# ETH_Design_ESP32.net
KiCad netlist of a schematic drawn in EAGLE
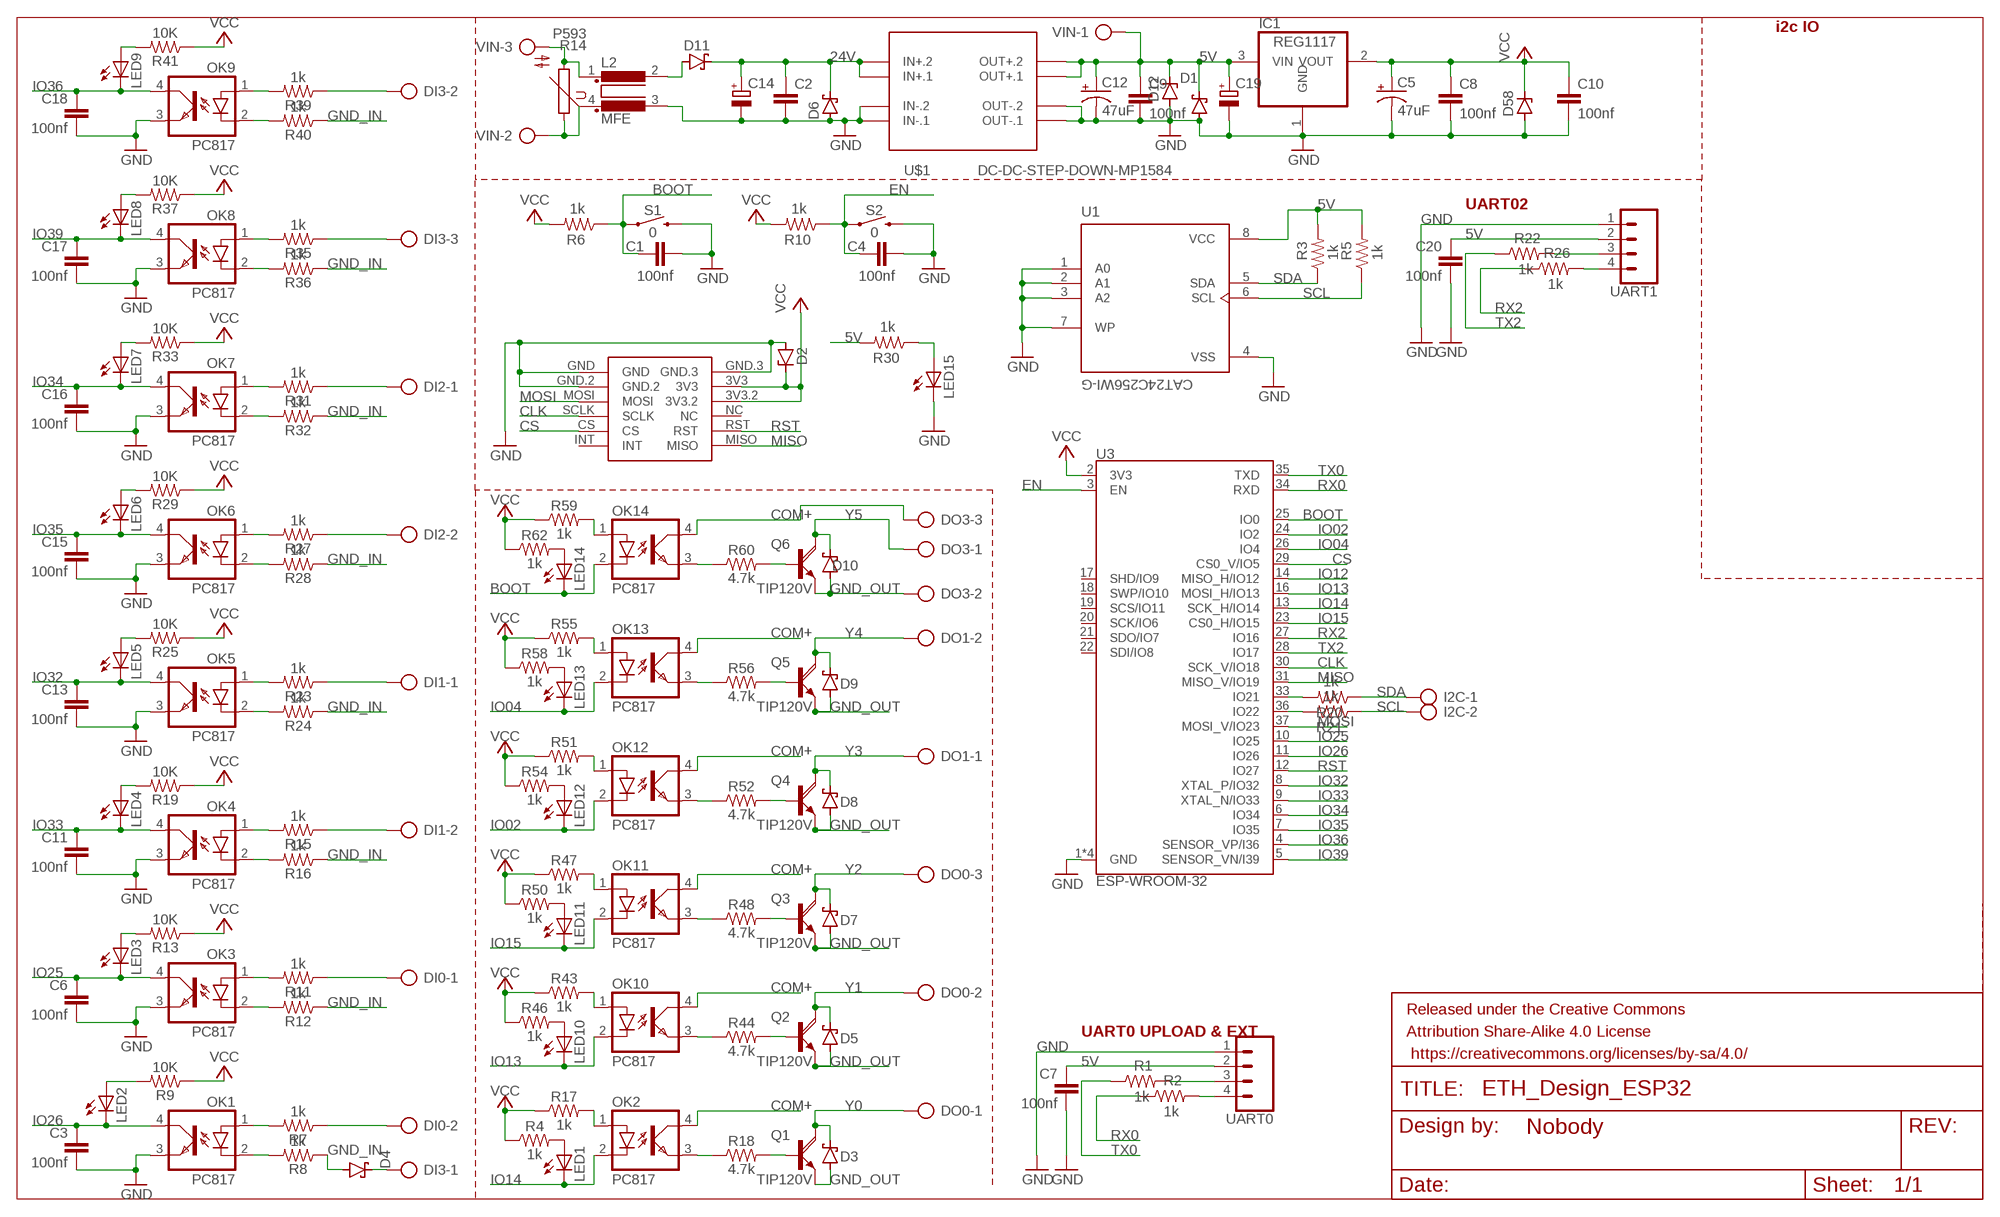
[diagram p0: schematic, sheet 1]

(export (version "E")
  (design (tool "Eeschema 10.0.6"))
  (components
    (comp (ref "C1")
      (value "100nf")
      (footprint "eagle-import:0805")
      (libsource (lib "eagle-import") (part "39NF-0805-50V-10%"))
    )
    (comp (ref "C2")
      (value "C-EUC1206K")
      (footprint "eagle-import:C1206K")
      (libsource (lib "eagle-import") (part "C-EUC1206K"))
    )
    (comp (ref "C3")
      (value "100nf")
      (footprint "eagle-import:0805")
      (libsource (lib "eagle-import") (part "39NF-0805-50V-10%"))
    )
    (comp (ref "C4")
      (value "100nf")
      (footprint "eagle-import:0805")
      (libsource (lib "eagle-import") (part "39NF-0805-50V-10%"))
    )
    (comp (ref "C5")
      (value "47uF")
      (footprint "eagle-import:EIA3528")
      (libsource (lib "eagle-import") (part "47UF-POLAR-EIA3528-10V-10%"))
    )
    (comp (ref "C6")
      (value "100nf")
      (footprint "eagle-import:0805")
      (libsource (lib "eagle-import") (part "39NF-0805-50V-10%"))
    )
    (comp (ref "C7")
      (value "100nf")
      (footprint "eagle-import:0805")
      (libsource (lib "eagle-import") (part "39NF-0805-50V-10%"))
    )
    (comp (ref "C8")
      (value "100nf")
      (footprint "eagle-import:0805")
      (libsource (lib "eagle-import") (part "39NF-0805-50V-10%"))
    )
    (comp (ref "C9")
      (value "100nf")
      (footprint "eagle-import:0805")
      (libsource (lib "eagle-import") (part "39NF-0805-50V-10%"))
    )
    (comp (ref "C10")
      (value "100nf")
      (footprint "eagle-import:0805")
      (libsource (lib "eagle-import") (part "39NF-0805-50V-10%"))
    )
    (comp (ref "C11")
      (value "100nf")
      (footprint "eagle-import:0805")
      (libsource (lib "eagle-import") (part "39NF-0805-50V-10%"))
    )
    (comp (ref "C12")
      (value "47uF")
      (footprint "eagle-import:EIA3528")
      (libsource (lib "eagle-import") (part "47UF-POLAR-EIA3528-10V-10%"))
    )
    (comp (ref "C13")
      (value "100nf")
      (footprint "eagle-import:0805")
      (libsource (lib "eagle-import") (part "39NF-0805-50V-10%"))
    )
    (comp (ref "C14")
      (value "CPOL-EUE2.5-7")
      (footprint "eagle-import:E2,5-7")
      (libsource (lib "eagle-import") (part "CPOL-EUE2.5-7"))
    )
    (comp (ref "C15")
      (value "100nf")
      (footprint "eagle-import:0805")
      (libsource (lib "eagle-import") (part "39NF-0805-50V-10%"))
    )
    (comp (ref "C16")
      (value "100nf")
      (footprint "eagle-import:0805")
      (libsource (lib "eagle-import") (part "39NF-0805-50V-10%"))
    )
    (comp (ref "C17")
      (value "100nf")
      (footprint "eagle-import:0805")
      (libsource (lib "eagle-import") (part "39NF-0805-50V-10%"))
    )
    (comp (ref "C18")
      (value "100nf")
      (footprint "eagle-import:0805")
      (libsource (lib "eagle-import") (part "39NF-0805-50V-10%"))
    )
    (comp (ref "C19")
      (value "CPOL-EUE2.5-7")
      (footprint "eagle-import:E2,5-7")
      (libsource (lib "eagle-import") (part "CPOL-EUE2.5-7"))
    )
    (comp (ref "C20")
      (value "100nf")
      (footprint "eagle-import:0805")
      (libsource (lib "eagle-import") (part "39NF-0805-50V-10%"))
    )
    (comp (ref "D1")
      (value "SCHOTTKY-DIODESMD")
      (footprint "eagle-import:SMB")
      (libsource (lib "eagle-import") (part "SCHOTTKY-DIODESMD"))
    )
    (comp (ref "D2")
      (value "ZENER-DIODESOD80C")
      (footprint "eagle-import:SOD80C")
      (libsource (lib "eagle-import") (part "ZENER-DIODESOD80C"))
    )
    (comp (ref "D3")
      (value "SCHOTTKY-DIODESMD")
      (footprint "eagle-import:SMB")
      (libsource (lib "eagle-import") (part "SCHOTTKY-DIODESMD"))
    )
    (comp (ref "D4")
      (value "SCHOTTKY-DIODESMD")
      (footprint "eagle-import:SMB")
      (libsource (lib "eagle-import") (part "SCHOTTKY-DIODESMD"))
    )
    (comp (ref "D5")
      (value "SCHOTTKY-DIODESMD")
      (footprint "eagle-import:SMB")
      (libsource (lib "eagle-import") (part "SCHOTTKY-DIODESMD"))
    )
    (comp (ref "D6")
      (value "SCHOTTKY-DIODESMD")
      (footprint "eagle-import:SMB")
      (libsource (lib "eagle-import") (part "SCHOTTKY-DIODESMD"))
    )
    (comp (ref "D7")
      (value "SCHOTTKY-DIODESMD")
      (footprint "eagle-import:SMB")
      (libsource (lib "eagle-import") (part "SCHOTTKY-DIODESMD"))
    )
    (comp (ref "D8")
      (value "SCHOTTKY-DIODESMD")
      (footprint "eagle-import:SMB")
      (libsource (lib "eagle-import") (part "SCHOTTKY-DIODESMD"))
    )
    (comp (ref "D9")
      (value "SCHOTTKY-DIODESMD")
      (footprint "eagle-import:SMB")
      (libsource (lib "eagle-import") (part "SCHOTTKY-DIODESMD"))
    )
    (comp (ref "D10")
      (value "SCHOTTKY-DIODESMD")
      (footprint "eagle-import:SMB")
      (libsource (lib "eagle-import") (part "SCHOTTKY-DIODESMD"))
    )
    (comp (ref "D11")
      (value "SCHOTTKY-DIODESMD")
      (footprint "eagle-import:SMB")
      (libsource (lib "eagle-import") (part "SCHOTTKY-DIODESMD"))
    )
    (comp (ref "D12")
      (value "ZENER-DIODESOD80C")
      (footprint "eagle-import:SOD80C")
      (libsource (lib "eagle-import") (part "ZENER-DIODESOD80C"))
    )
    (comp (ref "D58")
      (value "ZENER-DIODESOD80C")
      (footprint "eagle-import:SOD80C")
      (libsource (lib "eagle-import") (part "ZENER-DIODESOD80C"))
    )
    (comp (ref "DI0")
      (value "AK500/2")
      (footprint "eagle-import:AK500_2")
      (libsource (lib "eagle-import") (part "AK500/2"))
    )
    (comp (ref "DI1")
      (value "AK500/2")
      (footprint "eagle-import:AK500_2")
      (libsource (lib "eagle-import") (part "AK500/2"))
    )
    (comp (ref "DI2")
      (value "AK500/2")
      (footprint "eagle-import:AK500_2")
      (libsource (lib "eagle-import") (part "AK500/2"))
    )
    (comp (ref "DI3")
      (value "AK500/3")
      (footprint "eagle-import:AK500_3")
      (libsource (lib "eagle-import") (part "AK500/3"))
    )
    (comp (ref "DO0")
      (value "AK500/3")
      (footprint "eagle-import:AK500_3")
      (libsource (lib "eagle-import") (part "AK500/3"))
    )
    (comp (ref "DO1")
      (value "AK500/2")
      (footprint "eagle-import:AK500_2")
      (libsource (lib "eagle-import") (part "AK500/2"))
    )
    (comp (ref "DO3")
      (value "AK500/3")
      (footprint "eagle-import:AK500_3")
      (libsource (lib "eagle-import") (part "AK500/3"))
    )
    (comp (ref "FRAME1")
      (value "FRAME-LETTERNO_PACKAGE")
      (footprint "eagle-import:DUMMY")
      (fields (field (name "DESIGNER") "Nobody"))
      (libsource (lib "eagle-import") (part "FRAME-LETTERNO_PACKAGE"))
    )
    (comp (ref "I2C")
      (value "AK500/2")
      (footprint "eagle-import:AK500_2")
      (libsource (lib "eagle-import") (part "AK500/2"))
    )
    (comp (ref "IC1")
      (value "REG1117")
      (footprint "eagle-import:SOT223")
      (libsource (lib "eagle-import") (part "REG1117"))
    )
    (comp (ref "L2")
      (value "MFE")
      (footprint "eagle-import:MFE")
      (libsource (lib "eagle-import") (part "MFE"))
    )
    (comp (ref "LED1")
      (value "LEDCHIPLED_0805")
      (footprint "eagle-import:CHIPLED_0805")
      (libsource (lib "eagle-import") (part "LEDCHIPLED_0805"))
    )
    (comp (ref "LED2")
      (value "LEDCHIPLED_0805")
      (footprint "eagle-import:CHIPLED_0805")
      (libsource (lib "eagle-import") (part "LEDCHIPLED_0805"))
    )
    (comp (ref "LED3")
      (value "LEDCHIPLED_0805")
      (footprint "eagle-import:CHIPLED_0805")
      (libsource (lib "eagle-import") (part "LEDCHIPLED_0805"))
    )
    (comp (ref "LED4")
      (value "LEDCHIPLED_0805")
      (footprint "eagle-import:CHIPLED_0805")
      (libsource (lib "eagle-import") (part "LEDCHIPLED_0805"))
    )
    (comp (ref "LED5")
      (value "LEDCHIPLED_0805")
      (footprint "eagle-import:CHIPLED_0805")
      (libsource (lib "eagle-import") (part "LEDCHIPLED_0805"))
    )
    (comp (ref "LED6")
      (value "LEDCHIPLED_0805")
      (footprint "eagle-import:CHIPLED_0805")
      (libsource (lib "eagle-import") (part "LEDCHIPLED_0805"))
    )
    (comp (ref "LED7")
      (value "LEDCHIPLED_0805")
      (footprint "eagle-import:CHIPLED_0805")
      (libsource (lib "eagle-import") (part "LEDCHIPLED_0805"))
    )
    (comp (ref "LED8")
      (value "LEDCHIPLED_0805")
      (footprint "eagle-import:CHIPLED_0805")
      (libsource (lib "eagle-import") (part "LEDCHIPLED_0805"))
    )
    (comp (ref "LED9")
      (value "LEDCHIPLED_0805")
      (footprint "eagle-import:CHIPLED_0805")
      (libsource (lib "eagle-import") (part "LEDCHIPLED_0805"))
    )
    (comp (ref "LED10")
      (value "LEDCHIPLED_0805")
      (footprint "eagle-import:CHIPLED_0805")
      (libsource (lib "eagle-import") (part "LEDCHIPLED_0805"))
    )
    (comp (ref "LED11")
      (value "LEDCHIPLED_0805")
      (footprint "eagle-import:CHIPLED_0805")
      (libsource (lib "eagle-import") (part "LEDCHIPLED_0805"))
    )
    (comp (ref "LED12")
      (value "LEDCHIPLED_0805")
      (footprint "eagle-import:CHIPLED_0805")
      (libsource (lib "eagle-import") (part "LEDCHIPLED_0805"))
    )
    (comp (ref "LED13")
      (value "LEDCHIPLED_0805")
      (footprint "eagle-import:CHIPLED_0805")
      (libsource (lib "eagle-import") (part "LEDCHIPLED_0805"))
    )
    (comp (ref "LED14")
      (value "LEDCHIPLED_0805")
      (footprint "eagle-import:CHIPLED_0805")
      (libsource (lib "eagle-import") (part "LEDCHIPLED_0805"))
    )
    (comp (ref "LED15")
      (value "LEDCHIPLED_0805")
      (footprint "eagle-import:CHIPLED_0805")
      (libsource (lib "eagle-import") (part "LEDCHIPLED_0805"))
    )
    (comp (ref "OK1")
      (value "PC817")
      (footprint "eagle-import:DIL04")
      (fields (field (name "MPN") "PC817X4J000F"))
      (libsource (lib "eagle-import") (part "PC817"))
    )
    (comp (ref "OK2")
      (value "PC817")
      (footprint "eagle-import:DIL04")
      (fields (field (name "MPN") "PC817X4J000F"))
      (libsource (lib "eagle-import") (part "PC817"))
    )
    (comp (ref "OK3")
      (value "PC817")
      (footprint "eagle-import:DIL04")
      (fields (field (name "MPN") "PC817X4J000F"))
      (libsource (lib "eagle-import") (part "PC817"))
    )
    (comp (ref "OK4")
      (value "PC817")
      (footprint "eagle-import:DIL04")
      (fields (field (name "MPN") "PC817X4J000F"))
      (libsource (lib "eagle-import") (part "PC817"))
    )
    (comp (ref "OK5")
      (value "PC817")
      (footprint "eagle-import:DIL04")
      (fields (field (name "MPN") "PC817X4J000F"))
      (libsource (lib "eagle-import") (part "PC817"))
    )
    (comp (ref "OK6")
      (value "PC817")
      (footprint "eagle-import:DIL04")
      (fields (field (name "MPN") "PC817X4J000F"))
      (libsource (lib "eagle-import") (part "PC817"))
    )
    (comp (ref "OK7")
      (value "PC817")
      (footprint "eagle-import:DIL04")
      (fields (field (name "MPN") "PC817X4J000F"))
      (libsource (lib "eagle-import") (part "PC817"))
    )
    (comp (ref "OK8")
      (value "PC817")
      (footprint "eagle-import:DIL04")
      (fields (field (name "MPN") "PC817X4J000F"))
      (libsource (lib "eagle-import") (part "PC817"))
    )
    (comp (ref "OK9")
      (value "PC817")
      (footprint "eagle-import:DIL04")
      (fields (field (name "MPN") "PC817X4J000F"))
      (libsource (lib "eagle-import") (part "PC817"))
    )
    (comp (ref "OK10")
      (value "PC817")
      (footprint "eagle-import:DIL04")
      (fields (field (name "MPN") "PC817X4J000F"))
      (libsource (lib "eagle-import") (part "PC817"))
    )
    (comp (ref "OK11")
      (value "PC817")
      (footprint "eagle-import:DIL04")
      (fields (field (name "MPN") "PC817X4J000F"))
      (libsource (lib "eagle-import") (part "PC817"))
    )
    (comp (ref "OK12")
      (value "PC817")
      (footprint "eagle-import:DIL04")
      (fields (field (name "MPN") "PC817X4J000F"))
      (libsource (lib "eagle-import") (part "PC817"))
    )
    (comp (ref "OK13")
      (value "PC817")
      (footprint "eagle-import:DIL04")
      (fields (field (name "MPN") "PC817X4J000F"))
      (libsource (lib "eagle-import") (part "PC817"))
    )
    (comp (ref "OK14")
      (value "PC817")
      (footprint "eagle-import:DIL04")
      (fields (field (name "MPN") "PC817X4J000F"))
      (libsource (lib "eagle-import") (part "PC817"))
    )
    (comp (ref "Q1")
      (value "TIP120V")
      (footprint "eagle-import:TO220AV")
      (libsource (lib "eagle-import") (part "TIP120V"))
    )
    (comp (ref "Q2")
      (value "TIP120V")
      (footprint "eagle-import:TO220AV")
      (libsource (lib "eagle-import") (part "TIP120V"))
    )
    (comp (ref "Q3")
      (value "TIP120V")
      (footprint "eagle-import:TO220AV")
      (libsource (lib "eagle-import") (part "TIP120V"))
    )
    (comp (ref "Q4")
      (value "TIP120V")
      (footprint "eagle-import:TO220AV")
      (libsource (lib "eagle-import") (part "TIP120V"))
    )
    (comp (ref "Q5")
      (value "TIP120V")
      (footprint "eagle-import:TO220AV")
      (libsource (lib "eagle-import") (part "TIP120V"))
    )
    (comp (ref "Q6")
      (value "TIP120V")
      (footprint "eagle-import:TO220AV")
      (libsource (lib "eagle-import") (part "TIP120V"))
    )
    (comp (ref "R1")
      (value "1k")
      (footprint "eagle-import:0805")
      (libsource (lib "eagle-import") (part "0.3OHM-0805-1/8W-1%"))
    )
    (comp (ref "R2")
      (value "1k")
      (footprint "eagle-import:0805")
      (libsource (lib "eagle-import") (part "0.3OHM-0805-1/8W-1%"))
    )
    (comp (ref "R3")
      (value "1k")
      (footprint "eagle-import:0805")
      (libsource (lib "eagle-import") (part "0.3OHM-0805-1/8W-1%"))
    )
    (comp (ref "R4")
      (value "1k")
      (footprint "eagle-import:0805")
      (libsource (lib "eagle-import") (part "0.75OHM-0805-1/4W-1%"))
    )
    (comp (ref "R5")
      (value "1k")
      (footprint "eagle-import:0805")
      (libsource (lib "eagle-import") (part "0.3OHM-0805-1/8W-1%"))
    )
    (comp (ref "R6")
      (value "1k")
      (footprint "eagle-import:0805")
      (libsource (lib "eagle-import") (part "0.3OHM-0805-1/8W-1%"))
    )
    (comp (ref "R7")
      (value "1k")
      (footprint "eagle-import:0805")
      (libsource (lib "eagle-import") (part "0.75OHM-0805-1/4W-1%"))
    )
    (comp (ref "R8")
      (value "1k")
      (footprint "eagle-import:0805")
      (libsource (lib "eagle-import") (part "0.75OHM-0805-1/4W-1%"))
    )
    (comp (ref "R9")
      (value "10K")
      (footprint "eagle-import:0805")
      (libsource (lib "eagle-import") (part "0.75OHM-0805-1/4W-1%"))
    )
    (comp (ref "R10")
      (value "1k")
      (footprint "eagle-import:0805")
      (libsource (lib "eagle-import") (part "0.3OHM-0805-1/8W-1%"))
    )
    (comp (ref "R11")
      (value "1k")
      (footprint "eagle-import:0805")
      (libsource (lib "eagle-import") (part "0.75OHM-0805-1/4W-1%"))
    )
    (comp (ref "R12")
      (value "1k")
      (footprint "eagle-import:0805")
      (libsource (lib "eagle-import") (part "0.75OHM-0805-1/4W-1%"))
    )
    (comp (ref "R13")
      (value "10K")
      (footprint "eagle-import:0805")
      (libsource (lib "eagle-import") (part "0.75OHM-0805-1/4W-1%"))
    )
    (comp (ref "R14")
      (value "P593")
      (footprint "eagle-import:P593")
      (libsource (lib "eagle-import") (part "P593"))
    )
    (comp (ref "R15")
      (value "1k")
      (footprint "eagle-import:0805")
      (libsource (lib "eagle-import") (part "0.75OHM-0805-1/4W-1%"))
    )
    (comp (ref "R16")
      (value "1k")
      (footprint "eagle-import:0805")
      (libsource (lib "eagle-import") (part "0.75OHM-0805-1/4W-1%"))
    )
    (comp (ref "R17")
      (value "1k")
      (footprint "eagle-import:0805")
      (libsource (lib "eagle-import") (part "0.75OHM-0805-1/4W-1%"))
    )
    (comp (ref "R18")
      (value "4.7k")
      (footprint "eagle-import:0805")
      (libsource (lib "eagle-import") (part "0.75OHM-0805-1/4W-1%"))
    )
    (comp (ref "R19")
      (value "10K")
      (footprint "eagle-import:0805")
      (libsource (lib "eagle-import") (part "0.75OHM-0805-1/4W-1%"))
    )
    (comp (ref "R20")
      (value "1k")
      (footprint "eagle-import:0805")
      (libsource (lib "eagle-import") (part "0.3OHM-0805-1/8W-1%"))
    )
    (comp (ref "R21")
      (value "1k")
      (footprint "eagle-import:0805")
      (libsource (lib "eagle-import") (part "0.3OHM-0805-1/8W-1%"))
    )
    (comp (ref "R22")
      (value "1k")
      (footprint "eagle-import:0805")
      (libsource (lib "eagle-import") (part "0.3OHM-0805-1/8W-1%"))
    )
    (comp (ref "R23")
      (value "1k")
      (footprint "eagle-import:0805")
      (libsource (lib "eagle-import") (part "0.75OHM-0805-1/4W-1%"))
    )
    (comp (ref "R24")
      (value "1k")
      (footprint "eagle-import:0805")
      (libsource (lib "eagle-import") (part "0.75OHM-0805-1/4W-1%"))
    )
    (comp (ref "R25")
      (value "10K")
      (footprint "eagle-import:0805")
      (libsource (lib "eagle-import") (part "0.75OHM-0805-1/4W-1%"))
    )
    (comp (ref "R26")
      (value "1k")
      (footprint "eagle-import:0805")
      (libsource (lib "eagle-import") (part "0.3OHM-0805-1/8W-1%"))
    )
    (comp (ref "R27")
      (value "1k")
      (footprint "eagle-import:0805")
      (libsource (lib "eagle-import") (part "0.75OHM-0805-1/4W-1%"))
    )
    (comp (ref "R28")
      (value "1k")
      (footprint "eagle-import:0805")
      (libsource (lib "eagle-import") (part "0.75OHM-0805-1/4W-1%"))
    )
    (comp (ref "R29")
      (value "10K")
      (footprint "eagle-import:0805")
      (libsource (lib "eagle-import") (part "0.75OHM-0805-1/4W-1%"))
    )
    (comp (ref "R30")
      (value "1k")
      (footprint "eagle-import:0805")
      (libsource (lib "eagle-import") (part "0.3OHM-0805-1/8W-1%"))
    )
    (comp (ref "R31")
      (value "1k")
      (footprint "eagle-import:0805")
      (libsource (lib "eagle-import") (part "0.75OHM-0805-1/4W-1%"))
    )
    (comp (ref "R32")
      (value "1k")
      (footprint "eagle-import:0805")
      (libsource (lib "eagle-import") (part "0.75OHM-0805-1/4W-1%"))
    )
    (comp (ref "R33")
      (value "10K")
      (footprint "eagle-import:0805")
      (libsource (lib "eagle-import") (part "0.75OHM-0805-1/4W-1%"))
    )
    (comp (ref "R35")
      (value "1k")
      (footprint "eagle-import:0805")
      (libsource (lib "eagle-import") (part "0.75OHM-0805-1/4W-1%"))
    )
    (comp (ref "R36")
      (value "1k")
      (footprint "eagle-import:0805")
      (libsource (lib "eagle-import") (part "0.75OHM-0805-1/4W-1%"))
    )
    (comp (ref "R37")
      (value "10K")
      (footprint "eagle-import:0805")
      (libsource (lib "eagle-import") (part "0.75OHM-0805-1/4W-1%"))
    )
    (comp (ref "R39")
      (value "1k")
      (footprint "eagle-import:0805")
      (libsource (lib "eagle-import") (part "0.75OHM-0805-1/4W-1%"))
    )
    (comp (ref "R40")
      (value "1k")
      (footprint "eagle-import:0805")
      (libsource (lib "eagle-import") (part "0.75OHM-0805-1/4W-1%"))
    )
    (comp (ref "R41")
      (value "10K")
      (footprint "eagle-import:0805")
      (libsource (lib "eagle-import") (part "0.75OHM-0805-1/4W-1%"))
    )
    (comp (ref "R43")
      (value "1k")
      (footprint "eagle-import:0805")
      (libsource (lib "eagle-import") (part "0.75OHM-0805-1/4W-1%"))
    )
    (comp (ref "R44")
      (value "4.7k")
      (footprint "eagle-import:0805")
      (libsource (lib "eagle-import") (part "0.75OHM-0805-1/4W-1%"))
    )
    (comp (ref "R46")
      (value "1k")
      (footprint "eagle-import:0805")
      (libsource (lib "eagle-import") (part "0.75OHM-0805-1/4W-1%"))
    )
    (comp (ref "R47")
      (value "1k")
      (footprint "eagle-import:0805")
      (libsource (lib "eagle-import") (part "0.75OHM-0805-1/4W-1%"))
    )
    (comp (ref "R48")
      (value "4.7k")
      (footprint "eagle-import:0805")
      (libsource (lib "eagle-import") (part "0.75OHM-0805-1/4W-1%"))
    )
    (comp (ref "R50")
      (value "1k")
      (footprint "eagle-import:0805")
      (libsource (lib "eagle-import") (part "0.75OHM-0805-1/4W-1%"))
    )
    (comp (ref "R51")
      (value "1k")
      (footprint "eagle-import:0805")
      (libsource (lib "eagle-import") (part "0.75OHM-0805-1/4W-1%"))
    )
    (comp (ref "R52")
      (value "4.7k")
      (footprint "eagle-import:0805")
      (libsource (lib "eagle-import") (part "0.75OHM-0805-1/4W-1%"))
    )
    (comp (ref "R54")
      (value "1k")
      (footprint "eagle-import:0805")
      (libsource (lib "eagle-import") (part "0.75OHM-0805-1/4W-1%"))
    )
    (comp (ref "R55")
      (value "1k")
      (footprint "eagle-import:0805")
      (libsource (lib "eagle-import") (part "0.75OHM-0805-1/4W-1%"))
    )
    (comp (ref "R56")
      (value "4.7k")
      (footprint "eagle-import:0805")
      (libsource (lib "eagle-import") (part "0.75OHM-0805-1/4W-1%"))
    )
    (comp (ref "R58")
      (value "1k")
      (footprint "eagle-import:0805")
      (libsource (lib "eagle-import") (part "0.75OHM-0805-1/4W-1%"))
    )
    (comp (ref "R59")
      (value "1k")
      (footprint "eagle-import:0805")
      (libsource (lib "eagle-import") (part "0.75OHM-0805-1/4W-1%"))
    )
    (comp (ref "R60")
      (value "4.7k")
      (footprint "eagle-import:0805")
      (libsource (lib "eagle-import") (part "0.75OHM-0805-1/4W-1%"))
    )
    (comp (ref "R62")
      (value "1k")
      (footprint "eagle-import:0805")
      (libsource (lib "eagle-import") (part "0.75OHM-0805-1/4W-1%"))
    )
    (comp (ref "S1")
      (value "0")
      (footprint "eagle-import:TACTILE_SWITCH_PTH_6.0MM_KIT")
      (libsource (lib "eagle-import") (part "MOMENTARY-SWITCH-SPST-PTH-6.0MM-KIT"))
    )
    (comp (ref "S2")
      (value "0")
      (footprint "eagle-import:TACTILE_SWITCH_PTH_6.0MM_KIT")
      (libsource (lib "eagle-import") (part "MOMENTARY-SWITCH-SPST-PTH-6.0MM-KIT"))
    )
    (comp (ref "U$1")
      (value "DC-DC-STEP-DOWN-MP1584")
      (footprint "eagle-import:DC-DC-STEP-DOWN-MP1584")
      (libsource (lib "eagle-import") (part "DC-DC-STEP-DOWN-MP1584"))
    )
    (comp (ref "U$2")
      (value "MINI_W5500")
      (footprint "eagle-import:MINI_W5500")
      (libsource (lib "eagle-import") (part "MINI_W5500"))
    )
    (comp (ref "U1")
      (value "CAT24C256WI-G")
      (footprint "eagle-import:SOIC127P600X175-8N")
      (fields (field (name "MF") "ON Semiconductor"))
      (libsource (lib "eagle-import") (part "CAT24C256WI-G"))
    )
    (comp (ref "U3")
      (value "ESP-WROOM-32")
      (footprint "eagle-import:ESP-WROOM-32")
      (libsource (lib "eagle-import") (part "ESP-WROOM-32"))
    )
    (comp (ref "UART0")
      (value "CONN_04POLAR")
      (footprint "eagle-import:MOLEX-1X4")
      (libsource (lib "eagle-import") (part "CONN_04POLAR"))
    )
    (comp (ref "UART1")
      (value "CONN_04POLAR")
      (footprint "eagle-import:MOLEX-1X4")
      (libsource (lib "eagle-import") (part "CONN_04POLAR"))
    )
    (comp (ref "VIN")
      (value "AK500/3")
      (footprint "eagle-import:AK500_3")
      (libsource (lib "eagle-import") (part "AK500/3"))
    )
  )
  (nets
    (net (code "1") (name "/5V") (class "Default")
      (node (ref "C12") (pin "A") (pinfunction "+_A") (pintype "passive"))
      (node (ref "C19") (pin "+") (pinfunction "+_+") (pintype "passive"))
      (node (ref "C20") (pin "1") (pinfunction "1_1") (pintype "passive"))
      (node (ref "C7") (pin "1") (pinfunction "1_1") (pintype "passive"))
      (node (ref "C9") (pin "1") (pinfunction "1_1") (pintype "passive"))
      (node (ref "D1") (pin "C") (pinfunction "C_C") (pintype "passive"))
      (node (ref "D12") (pin "C") (pinfunction "C_C") (pintype "passive"))
      (node (ref "IC1") (pin "3") (pinfunction "VIN_3") (pintype "input"))
      (node (ref "R3") (pin "2") (pinfunction "2_2") (pintype "passive"))
      (node (ref "R30") (pin "2") (pinfunction "2_2") (pintype "passive"))
      (node (ref "R5") (pin "2") (pinfunction "2_2") (pintype "passive"))
      (node (ref "U$1") (pin "OUT+.1") (pinfunction "OUT+.1_OUT+.1") (pintype "bidirectional"))
      (node (ref "U$1") (pin "OUT+.2") (pinfunction "OUT+.2_OUT+.2") (pintype "bidirectional"))
      (node (ref "U1") (pin "8") (pinfunction "VCC_8") (pintype "power_in"))
      (node (ref "UART0") (pin "2") (pinfunction "2_2") (pintype "passive"))
      (node (ref "UART1") (pin "2") (pinfunction "2_2") (pintype "passive"))
      (node (ref "VIN") (pin "1") (pinfunction "KL_1") (pintype "passive"))
    )
    (net (code "2") (name "/24V") (class "Default")
      (node (ref "C14") (pin "+") (pinfunction "+_+") (pintype "passive"))
      (node (ref "C2") (pin "1") (pinfunction "1_1") (pintype "passive"))
      (node (ref "D11") (pin "C") (pinfunction "C_C") (pintype "passive"))
      (node (ref "D6") (pin "C") (pinfunction "C_C") (pintype "passive"))
      (node (ref "U$1") (pin "IN+.1") (pinfunction "IN+.1_IN+.1") (pintype "bidirectional"))
      (node (ref "U$1") (pin "IN+.2") (pinfunction "IN+.2_IN+.2") (pintype "bidirectional"))
    )
    (net (code "3") (name "/BOOT") (class "Default")
      (node (ref "C1") (pin "2") (pinfunction "2_2") (pintype "passive"))
      (node (ref "LED14") (pin "C") (pinfunction "C_C") (pintype "passive"))
      (node (ref "OK14") (pin "2") (pinfunction "C_2") (pintype "passive"))
      (node (ref "R6") (pin "1") (pinfunction "1_1") (pintype "passive"))
      (node (ref "S1") (pin "1") (pinfunction "1_1") (pintype "passive"))
      (node (ref "U3") (pin "25") (pinfunction "IO0_25") (pintype "bidirectional"))
    )
    (net (code "4") (name "/CLK") (class "Default")
      (node (ref "U$2") (pin "SCLK") (pinfunction "SCLK_SCLK") (pintype "bidirectional"))
      (node (ref "U3") (pin "30") (pinfunction "SCK_V/IO18_30") (pintype "bidirectional"))
    )
    (net (code "5") (name "/COM+") (class "Default")
      (node (ref "DO3") (pin "3") (pinfunction "KL_3") (pintype "passive"))
      (node (ref "OK10") (pin "4") (pinfunction "COL_4") (pintype "passive"))
      (node (ref "OK11") (pin "4") (pinfunction "COL_4") (pintype "passive"))
      (node (ref "OK12") (pin "4") (pinfunction "COL_4") (pintype "passive"))
      (node (ref "OK13") (pin "4") (pinfunction "COL_4") (pintype "passive"))
      (node (ref "OK14") (pin "4") (pinfunction "COL_4") (pintype "passive"))
      (node (ref "OK2") (pin "4") (pinfunction "COL_4") (pintype "passive"))
    )
    (net (code "6") (name "/CS") (class "Default")
      (node (ref "U$2") (pin "CS") (pinfunction "CS_CS") (pintype "bidirectional"))
      (node (ref "U3") (pin "29") (pinfunction "CS0_V/IO5_29") (pintype "bidirectional"))
    )
    (net (code "7") (name "/EN") (class "Default")
      (node (ref "C4") (pin "2") (pinfunction "2_2") (pintype "passive"))
      (node (ref "R10") (pin "1") (pinfunction "1_1") (pintype "passive"))
      (node (ref "S2") (pin "1") (pinfunction "1_1") (pintype "passive"))
      (node (ref "U3") (pin "3") (pinfunction "EN_3") (pintype "bidirectional"))
    )
    (net (code "8") (name "/GND_IN") (class "Default")
      (node (ref "D4") (pin "A") (pinfunction "A_A") (pintype "passive"))
      (node (ref "R12") (pin "1") (pinfunction "1_1") (pintype "passive"))
      (node (ref "R16") (pin "1") (pinfunction "1_1") (pintype "passive"))
      (node (ref "R24") (pin "1") (pinfunction "1_1") (pintype "passive"))
      (node (ref "R28") (pin "1") (pinfunction "1_1") (pintype "passive"))
      (node (ref "R32") (pin "1") (pinfunction "1_1") (pintype "passive"))
      (node (ref "R36") (pin "1") (pinfunction "1_1") (pintype "passive"))
      (node (ref "R40") (pin "1") (pinfunction "1_1") (pintype "passive"))
      (node (ref "R8") (pin "1") (pinfunction "1_1") (pintype "passive"))
    )
    (net (code "9") (name "/GND_OUT") (class "Default")
      (node (ref "D10") (pin "A") (pinfunction "A_A") (pintype "passive"))
      (node (ref "D3") (pin "A") (pinfunction "A_A") (pintype "passive"))
      (node (ref "D5") (pin "A") (pinfunction "A_A") (pintype "passive"))
      (node (ref "D7") (pin "A") (pinfunction "A_A") (pintype "passive"))
      (node (ref "D8") (pin "A") (pinfunction "A_A") (pintype "passive"))
      (node (ref "D9") (pin "A") (pinfunction "A_A") (pintype "passive"))
      (node (ref "DO3") (pin "2") (pinfunction "KL_2") (pintype "passive"))
      (node (ref "Q1") (pin "E") (pinfunction "E_E") (pintype "passive"))
      (node (ref "Q2") (pin "E") (pinfunction "E_E") (pintype "passive"))
      (node (ref "Q3") (pin "E") (pinfunction "E_E") (pintype "passive"))
      (node (ref "Q4") (pin "E") (pinfunction "E_E") (pintype "passive"))
      (node (ref "Q5") (pin "E") (pinfunction "E_E") (pintype "passive"))
      (node (ref "Q6") (pin "E") (pinfunction "E_E") (pintype "passive"))
    )
    (net (code "10") (name "/IO02") (class "Default")
      (node (ref "LED12") (pin "C") (pinfunction "C_C") (pintype "passive"))
      (node (ref "OK12") (pin "2") (pinfunction "C_2") (pintype "passive"))
      (node (ref "U3") (pin "24") (pinfunction "IO2_24") (pintype "bidirectional"))
    )
    (net (code "11") (name "/IO04") (class "Default")
      (node (ref "LED13") (pin "C") (pinfunction "C_C") (pintype "passive"))
      (node (ref "OK13") (pin "2") (pinfunction "C_2") (pintype "passive"))
      (node (ref "U3") (pin "26") (pinfunction "IO4_26") (pintype "bidirectional"))
    )
    (net (code "12") (name "/IO12") (class "Default")
      (node (ref "U3") (pin "14") (pinfunction "MISO_H/IO12_14") (pintype "bidirectional"))
    )
    (net (code "13") (name "/IO13") (class "Default")
      (node (ref "LED10") (pin "C") (pinfunction "C_C") (pintype "passive"))
      (node (ref "OK10") (pin "2") (pinfunction "C_2") (pintype "passive"))
      (node (ref "U3") (pin "16") (pinfunction "MOSI_H/IO13_16") (pintype "bidirectional"))
    )
    (net (code "14") (name "/IO14") (class "Default")
      (node (ref "LED1") (pin "C") (pinfunction "C_C") (pintype "passive"))
      (node (ref "OK2") (pin "2") (pinfunction "C_2") (pintype "passive"))
      (node (ref "U3") (pin "13") (pinfunction "SCK_H/IO14_13") (pintype "bidirectional"))
    )
    (net (code "15") (name "/IO15") (class "Default")
      (node (ref "LED11") (pin "C") (pinfunction "C_C") (pintype "passive"))
      (node (ref "OK11") (pin "2") (pinfunction "C_2") (pintype "passive"))
      (node (ref "U3") (pin "23") (pinfunction "CS0_H/IO15_23") (pintype "bidirectional"))
    )
    (net (code "16") (name "/IO25") (class "Default")
      (node (ref "C6") (pin "1") (pinfunction "1_1") (pintype "passive"))
      (node (ref "LED3") (pin "C") (pinfunction "C_C") (pintype "passive"))
      (node (ref "OK3") (pin "4") (pinfunction "COL_4") (pintype "passive"))
      (node (ref "U3") (pin "10") (pinfunction "IO25_10") (pintype "bidirectional"))
    )
    (net (code "17") (name "/IO26") (class "Default")
      (node (ref "C3") (pin "1") (pinfunction "1_1") (pintype "passive"))
      (node (ref "LED2") (pin "C") (pinfunction "C_C") (pintype "passive"))
      (node (ref "OK1") (pin "4") (pinfunction "COL_4") (pintype "passive"))
      (node (ref "U3") (pin "11") (pinfunction "IO26_11") (pintype "bidirectional"))
    )
    (net (code "18") (name "/IO32") (class "Default")
      (node (ref "C13") (pin "1") (pinfunction "1_1") (pintype "passive"))
      (node (ref "LED5") (pin "C") (pinfunction "C_C") (pintype "passive"))
      (node (ref "OK5") (pin "4") (pinfunction "COL_4") (pintype "passive"))
      (node (ref "U3") (pin "8") (pinfunction "XTAL_P/IO32_8") (pintype "bidirectional"))
    )
    (net (code "19") (name "/IO33") (class "Default")
      (node (ref "C11") (pin "1") (pinfunction "1_1") (pintype "passive"))
      (node (ref "LED4") (pin "C") (pinfunction "C_C") (pintype "passive"))
      (node (ref "OK4") (pin "4") (pinfunction "COL_4") (pintype "passive"))
      (node (ref "U3") (pin "9") (pinfunction "XTAL_N/IO33_9") (pintype "bidirectional"))
    )
    (net (code "20") (name "/IO34") (class "Default")
      (node (ref "C16") (pin "1") (pinfunction "1_1") (pintype "passive"))
      (node (ref "LED7") (pin "C") (pinfunction "C_C") (pintype "passive"))
      (node (ref "OK7") (pin "4") (pinfunction "COL_4") (pintype "passive"))
      (node (ref "U3") (pin "6") (pinfunction "IO34_6") (pintype "bidirectional"))
    )
    (net (code "21") (name "/IO35") (class "Default")
      (node (ref "C15") (pin "1") (pinfunction "1_1") (pintype "passive"))
      (node (ref "LED6") (pin "C") (pinfunction "C_C") (pintype "passive"))
      (node (ref "OK6") (pin "4") (pinfunction "COL_4") (pintype "passive"))
      (node (ref "U3") (pin "7") (pinfunction "IO35_7") (pintype "bidirectional"))
    )
    (net (code "22") (name "/IO36") (class "Default")
      (node (ref "C18") (pin "1") (pinfunction "1_1") (pintype "passive"))
      (node (ref "LED9") (pin "C") (pinfunction "C_C") (pintype "passive"))
      (node (ref "OK9") (pin "4") (pinfunction "COL_4") (pintype "passive"))
      (node (ref "U3") (pin "4") (pinfunction "SENSOR_VP/I36_4") (pintype "bidirectional"))
    )
    (net (code "23") (name "/IO39") (class "Default")
      (node (ref "C17") (pin "1") (pinfunction "1_1") (pintype "passive"))
      (node (ref "LED8") (pin "C") (pinfunction "C_C") (pintype "passive"))
      (node (ref "OK8") (pin "4") (pinfunction "COL_4") (pintype "passive"))
      (node (ref "U3") (pin "5") (pinfunction "SENSOR_VN/I39_5") (pintype "bidirectional"))
    )
    (net (code "24") (name "/MISO") (class "Default")
      (node (ref "U$2") (pin "MISO") (pinfunction "MISO_MISO") (pintype "bidirectional"))
      (node (ref "U3") (pin "31") (pinfunction "MISO_V/IO19_31") (pintype "bidirectional"))
    )
    (net (code "25") (name "/MOSI") (class "Default")
      (node (ref "U$2") (pin "MOSI") (pinfunction "MOSI_MOSI") (pintype "bidirectional"))
      (node (ref "U3") (pin "37") (pinfunction "MOSI_V/IO23_37") (pintype "bidirectional"))
    )
    (net (code "26") (name "/RST") (class "Default")
      (node (ref "U$2") (pin "RST") (pinfunction "RST_RST") (pintype "bidirectional"))
      (node (ref "U3") (pin "12") (pinfunction "IO27_12") (pintype "bidirectional"))
    )
    (net (code "27") (name "/RX0") (class "Default")
      (node (ref "R2") (pin "1") (pinfunction "1_1") (pintype "passive"))
      (node (ref "U3") (pin "34") (pinfunction "RXD_34") (pintype "bidirectional"))
    )
    (net (code "28") (name "/RX2") (class "Default")
      (node (ref "R26") (pin "1") (pinfunction "1_1") (pintype "passive"))
      (node (ref "U3") (pin "27") (pinfunction "IO16_27") (pintype "bidirectional"))
    )
    (net (code "29") (name "/SCL") (class "Default")
      (node (ref "I2C") (pin "2") (pinfunction "KL_2") (pintype "passive"))
      (node (ref "R21") (pin "1") (pinfunction "1_1") (pintype "passive"))
      (node (ref "R5") (pin "1") (pinfunction "1_1") (pintype "passive"))
      (node (ref "U1") (pin "6") (pinfunction "SCL_6") (pintype "input"))
    )
    (net (code "30") (name "/SDA") (class "Default")
      (node (ref "I2C") (pin "1") (pinfunction "KL_1") (pintype "passive"))
      (node (ref "R20") (pin "1") (pinfunction "1_1") (pintype "passive"))
      (node (ref "R3") (pin "1") (pinfunction "1_1") (pintype "passive"))
      (node (ref "U1") (pin "5") (pinfunction "SDA_5") (pintype "bidirectional"))
    )
    (net (code "31") (name "/TX0") (class "Default")
      (node (ref "R1") (pin "1") (pinfunction "1_1") (pintype "passive"))
      (node (ref "U3") (pin "35") (pinfunction "TXD_35") (pintype "bidirectional"))
    )
    (net (code "32") (name "/TX2") (class "Default")
      (node (ref "R22") (pin "1") (pinfunction "1_1") (pintype "passive"))
      (node (ref "U3") (pin "28") (pinfunction "IO17_28") (pintype "bidirectional"))
    )
    (net (code "33") (name "/Y0") (class "Default")
      (node (ref "D3") (pin "C") (pinfunction "C_C") (pintype "passive"))
      (node (ref "DO0") (pin "1") (pinfunction "KL_1") (pintype "passive"))
      (node (ref "Q1") (pin "C") (pinfunction "C_C") (pintype "passive"))
    )
    (net (code "34") (name "/Y1") (class "Default")
      (node (ref "D5") (pin "C") (pinfunction "C_C") (pintype "passive"))
      (node (ref "DO0") (pin "2") (pinfunction "KL_2") (pintype "passive"))
      (node (ref "Q2") (pin "C") (pinfunction "C_C") (pintype "passive"))
    )
    (net (code "35") (name "/Y2") (class "Default")
      (node (ref "D7") (pin "C") (pinfunction "C_C") (pintype "passive"))
      (node (ref "DO0") (pin "3") (pinfunction "KL_3") (pintype "passive"))
      (node (ref "Q3") (pin "C") (pinfunction "C_C") (pintype "passive"))
    )
    (net (code "36") (name "/Y3") (class "Default")
      (node (ref "D8") (pin "C") (pinfunction "C_C") (pintype "passive"))
      (node (ref "DO1") (pin "1") (pinfunction "KL_1") (pintype "passive"))
      (node (ref "Q4") (pin "C") (pinfunction "C_C") (pintype "passive"))
    )
    (net (code "37") (name "/Y4") (class "Default")
      (node (ref "D9") (pin "C") (pinfunction "C_C") (pintype "passive"))
      (node (ref "DO1") (pin "2") (pinfunction "KL_2") (pintype "passive"))
      (node (ref "Q5") (pin "C") (pinfunction "C_C") (pintype "passive"))
    )
    (net (code "38") (name "/Y5") (class "Default")
      (node (ref "D10") (pin "C") (pinfunction "C_C") (pintype "passive"))
      (node (ref "DO3") (pin "1") (pinfunction "KL_1") (pintype "passive"))
      (node (ref "Q6") (pin "C") (pinfunction "C_C") (pintype "passive"))
    )
    (net (code "39") (name "GND") (class "Default")
      (node (ref "C1") (pin "1") (pinfunction "1_1") (pintype "passive"))
      (node (ref "C10") (pin "2") (pinfunction "2_2") (pintype "passive"))
      (node (ref "C11") (pin "2") (pinfunction "2_2") (pintype "passive"))
      (node (ref "C12") (pin "C") (pinfunction "-_C") (pintype "passive"))
      (node (ref "C13") (pin "2") (pinfunction "2_2") (pintype "passive"))
      (node (ref "C14") (pin "-") (pinfunction "-_-") (pintype "passive"))
      (node (ref "C15") (pin "2") (pinfunction "2_2") (pintype "passive"))
      (node (ref "C16") (pin "2") (pinfunction "2_2") (pintype "passive"))
      (node (ref "C17") (pin "2") (pinfunction "2_2") (pintype "passive"))
      (node (ref "C18") (pin "2") (pinfunction "2_2") (pintype "passive"))
      (node (ref "C19") (pin "-") (pinfunction "-_-") (pintype "passive"))
      (node (ref "C2") (pin "2") (pinfunction "2_2") (pintype "passive"))
      (node (ref "C20") (pin "2") (pinfunction "2_2") (pintype "passive"))
      (node (ref "C3") (pin "2") (pinfunction "2_2") (pintype "passive"))
      (node (ref "C4") (pin "1") (pinfunction "1_1") (pintype "passive"))
      (node (ref "C5") (pin "C") (pinfunction "-_C") (pintype "passive"))
      (node (ref "C6") (pin "2") (pinfunction "2_2") (pintype "passive"))
      (node (ref "C7") (pin "2") (pinfunction "2_2") (pintype "passive"))
      (node (ref "C8") (pin "2") (pinfunction "2_2") (pintype "passive"))
      (node (ref "C9") (pin "2") (pinfunction "2_2") (pintype "passive"))
      (node (ref "D1") (pin "A") (pinfunction "A_A") (pintype "passive"))
      (node (ref "D12") (pin "A") (pinfunction "A_A") (pintype "passive"))
      (node (ref "D2") (pin "A") (pinfunction "A_A") (pintype "passive"))
      (node (ref "D58") (pin "A") (pinfunction "A_A") (pintype "passive"))
      (node (ref "D6") (pin "A") (pinfunction "A_A") (pintype "passive"))
      (node (ref "IC1") (pin "1") (pinfunction "GND_1") (pintype "power_in"))
      (node (ref "L2") (pin "3") (pinfunction "4_3") (pintype "passive"))
      (node (ref "LED15") (pin "C") (pinfunction "C_C") (pintype "passive"))
      (node (ref "OK1") (pin "3") (pinfunction "EMIT_3") (pintype "passive"))
      (node (ref "OK3") (pin "3") (pinfunction "EMIT_3") (pintype "passive"))
      (node (ref "OK4") (pin "3") (pinfunction "EMIT_3") (pintype "passive"))
      (node (ref "OK5") (pin "3") (pinfunction "EMIT_3") (pintype "passive"))
      (node (ref "OK6") (pin "3") (pinfunction "EMIT_3") (pintype "passive"))
      (node (ref "OK7") (pin "3") (pinfunction "EMIT_3") (pintype "passive"))
      (node (ref "OK8") (pin "3") (pinfunction "EMIT_3") (pintype "passive"))
      (node (ref "OK9") (pin "3") (pinfunction "EMIT_3") (pintype "passive"))
      (node (ref "S1") (pin "3") (pinfunction "2_3") (pintype "passive"))
      (node (ref "S2") (pin "3") (pinfunction "2_3") (pintype "passive"))
      (node (ref "U$1") (pin "IN-.1") (pinfunction "IN-.1_IN-.1") (pintype "bidirectional"))
      (node (ref "U$1") (pin "IN-.2") (pinfunction "IN-.2_IN-.2") (pintype "bidirectional"))
      (node (ref "U$1") (pin "OUT-.1") (pinfunction "OUT-.1_OUT-.1") (pintype "bidirectional"))
      (node (ref "U$1") (pin "OUT-.2") (pinfunction "OUT-.2_OUT-.2") (pintype "bidirectional"))
      (node (ref "U$2") (pin "GND") (pinfunction "GND_GND") (pintype "bidirectional"))
      (node (ref "U$2") (pin "GND.2") (pinfunction "GND.2_GND.2") (pintype "bidirectional"))
      (node (ref "U$2") (pin "GND.3") (pinfunction "GND.3_GND.3") (pintype "bidirectional"))
      (node (ref "U1") (pin "1") (pinfunction "A0_1") (pintype "input"))
      (node (ref "U1") (pin "2") (pinfunction "A1_2") (pintype "input"))
      (node (ref "U1") (pin "3") (pinfunction "A2_3") (pintype "input"))
      (node (ref "U1") (pin "4") (pinfunction "VSS_4") (pintype "power_in"))
      (node (ref "U1") (pin "7") (pinfunction "WP_7") (pintype "input"))
      (node (ref "U3") (pin "1") (pinfunction "GND_1") (pintype "bidirectional"))
      (node (ref "U3") (pin "15") (pinfunction "GND_15") (pintype "bidirectional"))
      (node (ref "U3") (pin "38") (pinfunction "GND_38") (pintype "bidirectional"))
      (node (ref "U3") (pin "GND") (pinfunction "GND_GND") (pintype "bidirectional"))
      (node (ref "UART0") (pin "1") (pinfunction "1_1") (pintype "passive"))
      (node (ref "UART1") (pin "1") (pinfunction "1_1") (pintype "passive"))
    )
    (net (code "40") (name "Net-(D11-PadA)") (class "Default")
      (node (ref "D11") (pin "A") (pinfunction "A_A") (pintype "passive"))
      (node (ref "L2") (pin "2") (pinfunction "2_2") (pintype "passive"))
    )
    (net (code "41") (name "Net-(DI0A-KL)") (class "Default")
      (node (ref "DI0") (pin "1") (pinfunction "KL_1") (pintype "passive"))
      (node (ref "R11") (pin "1") (pinfunction "1_1") (pintype "passive"))
    )
    (net (code "42") (name "Net-(DI0B-KL)") (class "Default")
      (node (ref "DI0") (pin "2") (pinfunction "KL_2") (pintype "passive"))
      (node (ref "R7") (pin "1") (pinfunction "1_1") (pintype "passive"))
    )
    (net (code "43") (name "Net-(DI1A-KL)") (class "Default")
      (node (ref "DI1") (pin "1") (pinfunction "KL_1") (pintype "passive"))
      (node (ref "R23") (pin "1") (pinfunction "1_1") (pintype "passive"))
    )
    (net (code "44") (name "Net-(DI1B-KL)") (class "Default")
      (node (ref "DI1") (pin "2") (pinfunction "KL_2") (pintype "passive"))
      (node (ref "R15") (pin "1") (pinfunction "1_1") (pintype "passive"))
    )
    (net (code "45") (name "Net-(DI2A-KL)") (class "Default")
      (node (ref "DI2") (pin "1") (pinfunction "KL_1") (pintype "passive"))
      (node (ref "R31") (pin "1") (pinfunction "1_1") (pintype "passive"))
    )
    (net (code "46") (name "Net-(DI2B-KL)") (class "Default")
      (node (ref "DI2") (pin "2") (pinfunction "KL_2") (pintype "passive"))
      (node (ref "R27") (pin "1") (pinfunction "1_1") (pintype "passive"))
    )
    (net (code "47") (name "Net-(DI3A-KL)") (class "Default")
      (node (ref "D4") (pin "C") (pinfunction "C_C") (pintype "passive"))
      (node (ref "DI3") (pin "1") (pinfunction "KL_1") (pintype "passive"))
    )
    (net (code "48") (name "Net-(DI3B-KL)") (class "Default")
      (node (ref "DI3") (pin "2") (pinfunction "KL_2") (pintype "passive"))
      (node (ref "R39") (pin "1") (pinfunction "1_1") (pintype "passive"))
    )
    (net (code "49") (name "Net-(DI3C-KL)") (class "Default")
      (node (ref "DI3") (pin "3") (pinfunction "KL_3") (pintype "passive"))
      (node (ref "R35") (pin "1") (pinfunction "1_1") (pintype "passive"))
    )
    (net (code "50") (name "Net-(L2-3)") (class "Default")
      (node (ref "L2") (pin "4") (pinfunction "3_4") (pintype "passive"))
      (node (ref "R14") (pin "1") (pinfunction "1_1") (pintype "passive"))
      (node (ref "VIN") (pin "2") (pinfunction "KL_2") (pintype "passive"))
    )
    (net (code "51") (name "Net-(LED1-PadA)") (class "Default")
      (node (ref "LED1") (pin "A") (pinfunction "A_A") (pintype "passive"))
      (node (ref "R4") (pin "2") (pinfunction "2_2") (pintype "passive"))
    )
    (net (code "52") (name "Net-(LED2-PadA)") (class "Default")
      (node (ref "LED2") (pin "A") (pinfunction "A_A") (pintype "passive"))
      (node (ref "R9") (pin "2") (pinfunction "2_2") (pintype "passive"))
    )
    (net (code "53") (name "Net-(LED3-PadA)") (class "Default")
      (node (ref "LED3") (pin "A") (pinfunction "A_A") (pintype "passive"))
      (node (ref "R13") (pin "2") (pinfunction "2_2") (pintype "passive"))
    )
    (net (code "54") (name "Net-(LED4-PadA)") (class "Default")
      (node (ref "LED4") (pin "A") (pinfunction "A_A") (pintype "passive"))
      (node (ref "R19") (pin "2") (pinfunction "2_2") (pintype "passive"))
    )
    (net (code "55") (name "Net-(LED5-PadA)") (class "Default")
      (node (ref "LED5") (pin "A") (pinfunction "A_A") (pintype "passive"))
      (node (ref "R25") (pin "2") (pinfunction "2_2") (pintype "passive"))
    )
    (net (code "56") (name "Net-(LED6-PadA)") (class "Default")
      (node (ref "LED6") (pin "A") (pinfunction "A_A") (pintype "passive"))
      (node (ref "R29") (pin "2") (pinfunction "2_2") (pintype "passive"))
    )
    (net (code "57") (name "Net-(LED7-PadA)") (class "Default")
      (node (ref "LED7") (pin "A") (pinfunction "A_A") (pintype "passive"))
      (node (ref "R33") (pin "2") (pinfunction "2_2") (pintype "passive"))
    )
    (net (code "58") (name "Net-(LED8-PadA)") (class "Default")
      (node (ref "LED8") (pin "A") (pinfunction "A_A") (pintype "passive"))
      (node (ref "R37") (pin "2") (pinfunction "2_2") (pintype "passive"))
    )
    (net (code "59") (name "Net-(LED9-PadA)") (class "Default")
      (node (ref "LED9") (pin "A") (pinfunction "A_A") (pintype "passive"))
      (node (ref "R41") (pin "2") (pinfunction "2_2") (pintype "passive"))
    )
    (net (code "60") (name "Net-(LED10-PadA)") (class "Default")
      (node (ref "LED10") (pin "A") (pinfunction "A_A") (pintype "passive"))
      (node (ref "R46") (pin "2") (pinfunction "2_2") (pintype "passive"))
    )
    (net (code "61") (name "Net-(LED11-PadA)") (class "Default")
      (node (ref "LED11") (pin "A") (pinfunction "A_A") (pintype "passive"))
      (node (ref "R50") (pin "2") (pinfunction "2_2") (pintype "passive"))
    )
    (net (code "62") (name "Net-(LED12-PadA)") (class "Default")
      (node (ref "LED12") (pin "A") (pinfunction "A_A") (pintype "passive"))
      (node (ref "R54") (pin "2") (pinfunction "2_2") (pintype "passive"))
    )
    (net (code "63") (name "Net-(LED13-PadA)") (class "Default")
      (node (ref "LED13") (pin "A") (pinfunction "A_A") (pintype "passive"))
      (node (ref "R58") (pin "2") (pinfunction "2_2") (pintype "passive"))
    )
    (net (code "64") (name "Net-(LED14-PadA)") (class "Default")
      (node (ref "LED14") (pin "A") (pinfunction "A_A") (pintype "passive"))
      (node (ref "R62") (pin "2") (pinfunction "2_2") (pintype "passive"))
    )
    (net (code "65") (name "Net-(LED15-PadA)") (class "Default")
      (node (ref "LED15") (pin "A") (pinfunction "A_A") (pintype "passive"))
      (node (ref "R30") (pin "1") (pinfunction "1_1") (pintype "passive"))
    )
    (net (code "66") (name "Net-(OK1-A)") (class "Default")
      (node (ref "OK1") (pin "1") (pinfunction "A_1") (pintype "passive"))
      (node (ref "R7") (pin "2") (pinfunction "2_2") (pintype "passive"))
    )
    (net (code "67") (name "Net-(OK1-C)") (class "Default")
      (node (ref "OK1") (pin "2") (pinfunction "C_2") (pintype "passive"))
      (node (ref "R8") (pin "2") (pinfunction "2_2") (pintype "passive"))
    )
    (net (code "68") (name "Net-(OK2-A)") (class "Default")
      (node (ref "OK2") (pin "1") (pinfunction "A_1") (pintype "passive"))
      (node (ref "R17") (pin "2") (pinfunction "2_2") (pintype "passive"))
    )
    (net (code "69") (name "Net-(OK2-EMIT)") (class "Default")
      (node (ref "OK2") (pin "3") (pinfunction "EMIT_3") (pintype "passive"))
      (node (ref "R18") (pin "1") (pinfunction "1_1") (pintype "passive"))
    )
    (net (code "70") (name "Net-(OK3-A)") (class "Default")
      (node (ref "OK3") (pin "1") (pinfunction "A_1") (pintype "passive"))
      (node (ref "R11") (pin "2") (pinfunction "2_2") (pintype "passive"))
    )
    (net (code "71") (name "Net-(OK3-C)") (class "Default")
      (node (ref "OK3") (pin "2") (pinfunction "C_2") (pintype "passive"))
      (node (ref "R12") (pin "2") (pinfunction "2_2") (pintype "passive"))
    )
    (net (code "72") (name "Net-(OK4-A)") (class "Default")
      (node (ref "OK4") (pin "1") (pinfunction "A_1") (pintype "passive"))
      (node (ref "R15") (pin "2") (pinfunction "2_2") (pintype "passive"))
    )
    (net (code "73") (name "Net-(OK4-C)") (class "Default")
      (node (ref "OK4") (pin "2") (pinfunction "C_2") (pintype "passive"))
      (node (ref "R16") (pin "2") (pinfunction "2_2") (pintype "passive"))
    )
    (net (code "74") (name "Net-(OK5-A)") (class "Default")
      (node (ref "OK5") (pin "1") (pinfunction "A_1") (pintype "passive"))
      (node (ref "R23") (pin "2") (pinfunction "2_2") (pintype "passive"))
    )
    (net (code "75") (name "Net-(OK5-C)") (class "Default")
      (node (ref "OK5") (pin "2") (pinfunction "C_2") (pintype "passive"))
      (node (ref "R24") (pin "2") (pinfunction "2_2") (pintype "passive"))
    )
    (net (code "76") (name "Net-(OK6-A)") (class "Default")
      (node (ref "OK6") (pin "1") (pinfunction "A_1") (pintype "passive"))
      (node (ref "R27") (pin "2") (pinfunction "2_2") (pintype "passive"))
    )
    (net (code "77") (name "Net-(OK6-C)") (class "Default")
      (node (ref "OK6") (pin "2") (pinfunction "C_2") (pintype "passive"))
      (node (ref "R28") (pin "2") (pinfunction "2_2") (pintype "passive"))
    )
    (net (code "78") (name "Net-(OK7-A)") (class "Default")
      (node (ref "OK7") (pin "1") (pinfunction "A_1") (pintype "passive"))
      (node (ref "R31") (pin "2") (pinfunction "2_2") (pintype "passive"))
    )
    (net (code "79") (name "Net-(OK7-C)") (class "Default")
      (node (ref "OK7") (pin "2") (pinfunction "C_2") (pintype "passive"))
      (node (ref "R32") (pin "2") (pinfunction "2_2") (pintype "passive"))
    )
    (net (code "80") (name "Net-(OK8-A)") (class "Default")
      (node (ref "OK8") (pin "1") (pinfunction "A_1") (pintype "passive"))
      (node (ref "R35") (pin "2") (pinfunction "2_2") (pintype "passive"))
    )
    (net (code "81") (name "Net-(OK8-C)") (class "Default")
      (node (ref "OK8") (pin "2") (pinfunction "C_2") (pintype "passive"))
      (node (ref "R36") (pin "2") (pinfunction "2_2") (pintype "passive"))
    )
    (net (code "82") (name "Net-(OK9-A)") (class "Default")
      (node (ref "OK9") (pin "1") (pinfunction "A_1") (pintype "passive"))
      (node (ref "R39") (pin "2") (pinfunction "2_2") (pintype "passive"))
    )
    (net (code "83") (name "Net-(OK9-C)") (class "Default")
      (node (ref "OK9") (pin "2") (pinfunction "C_2") (pintype "passive"))
      (node (ref "R40") (pin "2") (pinfunction "2_2") (pintype "passive"))
    )
    (net (code "84") (name "Net-(OK10-A)") (class "Default")
      (node (ref "OK10") (pin "1") (pinfunction "A_1") (pintype "passive"))
      (node (ref "R43") (pin "2") (pinfunction "2_2") (pintype "passive"))
    )
    (net (code "85") (name "Net-(OK10-EMIT)") (class "Default")
      (node (ref "OK10") (pin "3") (pinfunction "EMIT_3") (pintype "passive"))
      (node (ref "R44") (pin "1") (pinfunction "1_1") (pintype "passive"))
    )
    (net (code "86") (name "Net-(OK11-A)") (class "Default")
      (node (ref "OK11") (pin "1") (pinfunction "A_1") (pintype "passive"))
      (node (ref "R47") (pin "2") (pinfunction "2_2") (pintype "passive"))
    )
    (net (code "87") (name "Net-(OK11-EMIT)") (class "Default")
      (node (ref "OK11") (pin "3") (pinfunction "EMIT_3") (pintype "passive"))
      (node (ref "R48") (pin "1") (pinfunction "1_1") (pintype "passive"))
    )
    (net (code "88") (name "Net-(OK12-A)") (class "Default")
      (node (ref "OK12") (pin "1") (pinfunction "A_1") (pintype "passive"))
      (node (ref "R51") (pin "2") (pinfunction "2_2") (pintype "passive"))
    )
    (net (code "89") (name "Net-(OK12-EMIT)") (class "Default")
      (node (ref "OK12") (pin "3") (pinfunction "EMIT_3") (pintype "passive"))
      (node (ref "R52") (pin "1") (pinfunction "1_1") (pintype "passive"))
    )
    (net (code "90") (name "Net-(OK13-A)") (class "Default")
      (node (ref "OK13") (pin "1") (pinfunction "A_1") (pintype "passive"))
      (node (ref "R55") (pin "2") (pinfunction "2_2") (pintype "passive"))
    )
    (net (code "91") (name "Net-(OK13-EMIT)") (class "Default")
      (node (ref "OK13") (pin "3") (pinfunction "EMIT_3") (pintype "passive"))
      (node (ref "R56") (pin "1") (pinfunction "1_1") (pintype "passive"))
    )
    (net (code "92") (name "Net-(OK14-A)") (class "Default")
      (node (ref "OK14") (pin "1") (pinfunction "A_1") (pintype "passive"))
      (node (ref "R59") (pin "2") (pinfunction "2_2") (pintype "passive"))
    )
    (net (code "93") (name "Net-(OK14-EMIT)") (class "Default")
      (node (ref "OK14") (pin "3") (pinfunction "EMIT_3") (pintype "passive"))
      (node (ref "R60") (pin "1") (pinfunction "1_1") (pintype "passive"))
    )
    (net (code "94") (name "Net-(Q1-PadB)") (class "Default")
      (node (ref "Q1") (pin "B") (pinfunction "B_B") (pintype "passive"))
      (node (ref "R18") (pin "2") (pinfunction "2_2") (pintype "passive"))
    )
    (net (code "95") (name "Net-(Q2-PadB)") (class "Default")
      (node (ref "Q2") (pin "B") (pinfunction "B_B") (pintype "passive"))
      (node (ref "R44") (pin "2") (pinfunction "2_2") (pintype "passive"))
    )
    (net (code "96") (name "Net-(Q3-PadB)") (class "Default")
      (node (ref "Q3") (pin "B") (pinfunction "B_B") (pintype "passive"))
      (node (ref "R48") (pin "2") (pinfunction "2_2") (pintype "passive"))
    )
    (net (code "97") (name "Net-(Q4-PadB)") (class "Default")
      (node (ref "Q4") (pin "B") (pinfunction "B_B") (pintype "passive"))
      (node (ref "R52") (pin "2") (pinfunction "2_2") (pintype "passive"))
    )
    (net (code "98") (name "Net-(Q5-PadB)") (class "Default")
      (node (ref "Q5") (pin "B") (pinfunction "B_B") (pintype "passive"))
      (node (ref "R56") (pin "2") (pinfunction "2_2") (pintype "passive"))
    )
    (net (code "99") (name "Net-(Q6-PadB)") (class "Default")
      (node (ref "Q6") (pin "B") (pinfunction "B_B") (pintype "passive"))
      (node (ref "R60") (pin "2") (pinfunction "2_2") (pintype "passive"))
    )
    (net (code "100") (name "Net-(R1-Pad2)") (class "Default")
      (node (ref "R1") (pin "2") (pinfunction "2_2") (pintype "passive"))
      (node (ref "UART0") (pin "3") (pinfunction "3_3") (pintype "passive"))
    )
    (net (code "101") (name "Net-(R2-Pad2)") (class "Default")
      (node (ref "R2") (pin "2") (pinfunction "2_2") (pintype "passive"))
      (node (ref "UART0") (pin "4") (pinfunction "4_4") (pintype "passive"))
    )
    (net (code "102") (name "Net-(R22-Pad2)") (class "Default")
      (node (ref "R22") (pin "2") (pinfunction "2_2") (pintype "passive"))
      (node (ref "UART1") (pin "3") (pinfunction "3_3") (pintype "passive"))
    )
    (net (code "103") (name "Net-(R26-Pad2)") (class "Default")
      (node (ref "R26") (pin "2") (pinfunction "2_2") (pintype "passive"))
      (node (ref "UART1") (pin "4") (pinfunction "4_4") (pintype "passive"))
    )
    (net (code "104") (name "Net-(U3-IO21)") (class "Default")
      (node (ref "R20") (pin "2") (pinfunction "2_2") (pintype "passive"))
      (node (ref "U3") (pin "33") (pinfunction "IO21_33") (pintype "bidirectional"))
    )
    (net (code "105") (name "Net-(U3-IO22)") (class "Default")
      (node (ref "R21") (pin "2") (pinfunction "2_2") (pintype "passive"))
      (node (ref "U3") (pin "36") (pinfunction "IO22_36") (pintype "bidirectional"))
    )
    (net (code "106") (name "Net-(VINC-KL)") (class "Default")
      (node (ref "L2") (pin "1") (pinfunction "1_1") (pintype "passive"))
      (node (ref "R14") (pin "2") (pinfunction "2_2") (pintype "passive"))
      (node (ref "VIN") (pin "3") (pinfunction "KL_3") (pintype "passive"))
    )
    (net (code "107") (name "VCC") (class "Default")
      (node (ref "C10") (pin "1") (pinfunction "1_1") (pintype "passive"))
      (node (ref "C5") (pin "A") (pinfunction "+_A") (pintype "passive"))
      (node (ref "C8") (pin "1") (pinfunction "1_1") (pintype "passive"))
      (node (ref "D2") (pin "C") (pinfunction "C_C") (pintype "passive"))
      (node (ref "D58") (pin "C") (pinfunction "C_C") (pintype "passive"))
      (node (ref "IC1") (pin "2") (pinfunction "VOUT_2") (pintype "output"))
      (node (ref "R10") (pin "2") (pinfunction "2_2") (pintype "passive"))
      (node (ref "R13") (pin "1") (pinfunction "1_1") (pintype "passive"))
      (node (ref "R17") (pin "1") (pinfunction "1_1") (pintype "passive"))
      (node (ref "R19") (pin "1") (pinfunction "1_1") (pintype "passive"))
      (node (ref "R25") (pin "1") (pinfunction "1_1") (pintype "passive"))
      (node (ref "R29") (pin "1") (pinfunction "1_1") (pintype "passive"))
      (node (ref "R33") (pin "1") (pinfunction "1_1") (pintype "passive"))
      (node (ref "R37") (pin "1") (pinfunction "1_1") (pintype "passive"))
      (node (ref "R4") (pin "1") (pinfunction "1_1") (pintype "passive"))
      (node (ref "R41") (pin "1") (pinfunction "1_1") (pintype "passive"))
      (node (ref "R43") (pin "1") (pinfunction "1_1") (pintype "passive"))
      (node (ref "R46") (pin "1") (pinfunction "1_1") (pintype "passive"))
      (node (ref "R47") (pin "1") (pinfunction "1_1") (pintype "passive"))
      (node (ref "R50") (pin "1") (pinfunction "1_1") (pintype "passive"))
      (node (ref "R51") (pin "1") (pinfunction "1_1") (pintype "passive"))
      (node (ref "R54") (pin "1") (pinfunction "1_1") (pintype "passive"))
      (node (ref "R55") (pin "1") (pinfunction "1_1") (pintype "passive"))
      (node (ref "R58") (pin "1") (pinfunction "1_1") (pintype "passive"))
      (node (ref "R59") (pin "1") (pinfunction "1_1") (pintype "passive"))
      (node (ref "R6") (pin "2") (pinfunction "2_2") (pintype "passive"))
      (node (ref "R62") (pin "1") (pinfunction "1_1") (pintype "passive"))
      (node (ref "R9") (pin "1") (pinfunction "1_1") (pintype "passive"))
      (node (ref "U$2") (pin "3V3") (pinfunction "3V3_3V3") (pintype "bidirectional"))
      (node (ref "U$2") (pin "3V3.2") (pinfunction "3V3.2_3V3.2") (pintype "bidirectional"))
      (node (ref "U3") (pin "2") (pinfunction "3V3_2") (pintype "bidirectional"))
    )
    (net (code "108") (name "unconnected-(U$2-PadINT)") (class "Default")
      (node (ref "U$2") (pin "INT") (pinfunction "INT_INT") (pintype "bidirectional"))
    )
    (net (code "109") (name "unconnected-(U$2-PadNC)") (class "Default")
      (node (ref "U$2") (pin "NC") (pinfunction "NC_NC") (pintype "bidirectional"))
    )
    (net (code "110") (name "unconnected-(U3-SCK{slash}IO6-Pad20)") (class "Default")
      (node (ref "U3") (pin "20") (pinfunction "SCK/IO6_20") (pintype "bidirectional"))
    )
    (net (code "111") (name "unconnected-(U3-SCS{slash}IO11-Pad19)") (class "Default")
      (node (ref "U3") (pin "19") (pinfunction "SCS/IO11_19") (pintype "bidirectional"))
    )
    (net (code "112") (name "unconnected-(U3-SDI{slash}IO8-Pad22)") (class "Default")
      (node (ref "U3") (pin "22") (pinfunction "SDI/IO8_22") (pintype "bidirectional"))
    )
    (net (code "113") (name "unconnected-(U3-SDO{slash}IO7-Pad21)") (class "Default")
      (node (ref "U3") (pin "21") (pinfunction "SDO/IO7_21") (pintype "bidirectional"))
    )
    (net (code "114") (name "unconnected-(U3-SHD{slash}IO9-Pad17)") (class "Default")
      (node (ref "U3") (pin "17") (pinfunction "SHD/IO9_17") (pintype "bidirectional"))
    )
    (net (code "115") (name "unconnected-(U3-SWP{slash}IO10-Pad18)") (class "Default")
      (node (ref "U3") (pin "18") (pinfunction "SWP/IO10_18") (pintype "bidirectional"))
    )
  )
)
